# rfboard.net
KiCad netlist of a schematic drawn in EAGLE
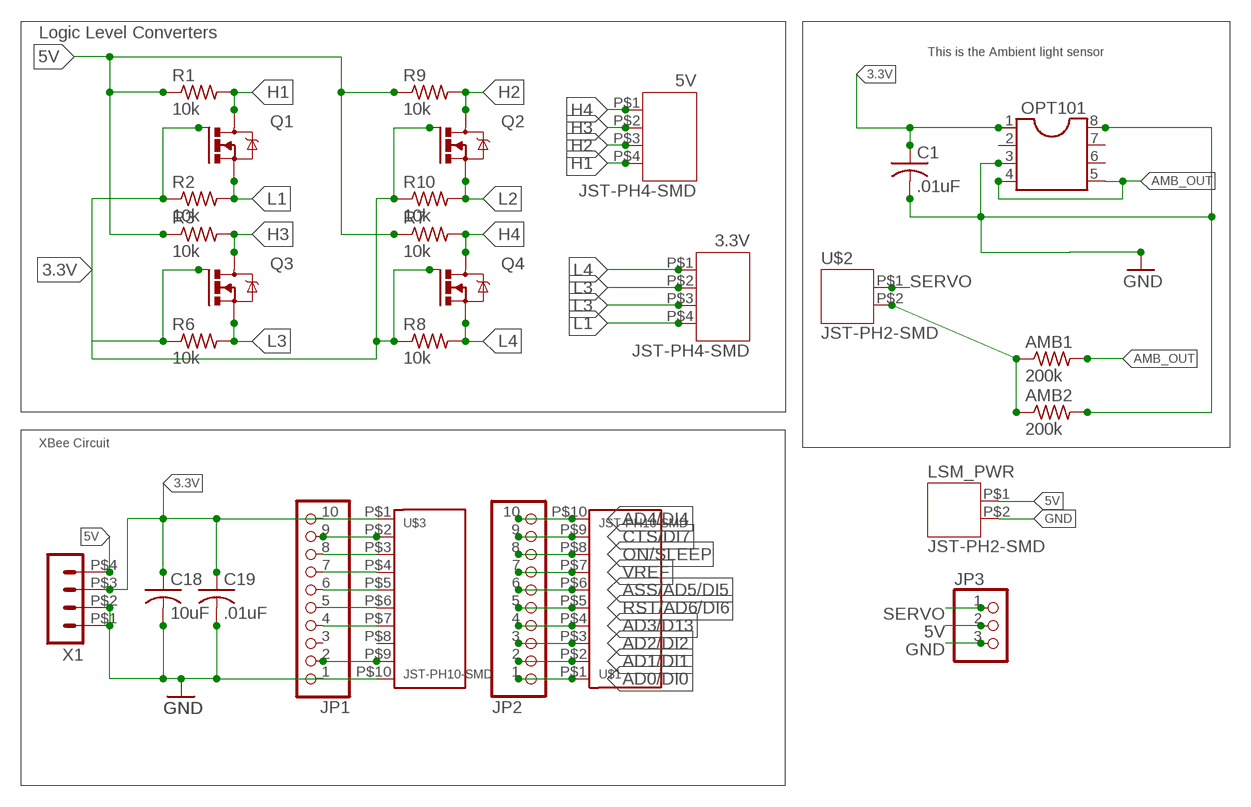
[diagram p0: schematic, sheet 1]

(export (version "E")
  (design (tool "Eeschema 10.0.6"))
  (components
    (comp (ref "3.3V")
      (value "JST-PH4-SMD")
      (footprint "eagle-import:JST-PH4-SMD")
      (libsource (lib "eagle-import") (part "JST-PH4-SMD"))
    )
    (comp (ref "5V")
      (value "JST-PH4-SMD")
      (footprint "eagle-import:JST-PH4-SMD")
      (libsource (lib "eagle-import") (part "JST-PH4-SMD"))
    )
    (comp (ref "AMB1")
      (value "200k")
      (footprint "eagle-import:R0805")
      (libsource (lib "eagle-import") (part "R-US_R0805"))
    )
    (comp (ref "AMB2")
      (value "200k")
      (footprint "eagle-import:R0805")
      (libsource (lib "eagle-import") (part "R-US_R0805"))
    )
    (comp (ref "C1")
      (value ".01uF")
      (footprint "eagle-import:C0805K")
      (libsource (lib "eagle-import") (part "C-USC0805K"))
    )
    (comp (ref "C18")
      (value "10uF")
      (footprint "eagle-import:C1206K")
      (libsource (lib "eagle-import") (part "C-USC1206K"))
    )
    (comp (ref "C19")
      (value ".01uF")
      (footprint "eagle-import:C0805K")
      (libsource (lib "eagle-import") (part "C-USC0805K"))
    )
    (comp (ref "JP1")
      (value "PINHD-1X10_2.00")
      (footprint "eagle-import:1X10M")
      (libsource (lib "eagle-import") (part "PINHD-1X10_2.00"))
    )
    (comp (ref "JP2")
      (value "PINHD-1X10_2.00")
      (footprint "eagle-import:1X10M")
      (libsource (lib "eagle-import") (part "PINHD-1X10_2.00"))
    )
    (comp (ref "JP3")
      (value "PINHD-1X3")
      (footprint "eagle-import:1X03")
      (libsource (lib "eagle-import") (part "PINHD-1X3"))
    )
    (comp (ref "LSM_PWR")
      (value "JST-PH2-SMD")
      (footprint "eagle-import:JST-PH2-SMD")
      (libsource (lib "eagle-import") (part "JST-PH2-SMD"))
    )
    (comp (ref "OPT101")
      (value "DIL8")
      (footprint "eagle-import:DIL08")
      (libsource (lib "eagle-import") (part "DIL8"))
    )
    (comp (ref "Q1")
      (value "IRLML5203")
      (footprint "eagle-import:MICRO3")
      (libsource (lib "eagle-import") (part "IRLML5203"))
    )
    (comp (ref "Q2")
      (value "IRLML5203")
      (footprint "eagle-import:MICRO3")
      (libsource (lib "eagle-import") (part "IRLML5203"))
    )
    (comp (ref "Q3")
      (value "IRLML5203")
      (footprint "eagle-import:MICRO3")
      (libsource (lib "eagle-import") (part "IRLML5203"))
    )
    (comp (ref "Q4")
      (value "IRLML5203")
      (footprint "eagle-import:MICRO3")
      (libsource (lib "eagle-import") (part "IRLML5203"))
    )
    (comp (ref "R1")
      (value "10k")
      (footprint "eagle-import:R0805")
      (libsource (lib "eagle-import") (part "R-US_R0805"))
    )
    (comp (ref "R2")
      (value "10k")
      (footprint "eagle-import:R0805")
      (libsource (lib "eagle-import") (part "R-US_R0805"))
    )
    (comp (ref "R3")
      (value "10k")
      (footprint "eagle-import:R0805")
      (libsource (lib "eagle-import") (part "R-US_R0805"))
    )
    (comp (ref "R6")
      (value "10k")
      (footprint "eagle-import:R0805")
      (libsource (lib "eagle-import") (part "R-US_R0805"))
    )
    (comp (ref "R7")
      (value "10k")
      (footprint "eagle-import:R0805")
      (libsource (lib "eagle-import") (part "R-US_R0805"))
    )
    (comp (ref "R8")
      (value "10k")
      (footprint "eagle-import:R0805")
      (libsource (lib "eagle-import") (part "R-US_R0805"))
    )
    (comp (ref "R9")
      (value "10k")
      (footprint "eagle-import:R0805")
      (libsource (lib "eagle-import") (part "R-US_R0805"))
    )
    (comp (ref "R10")
      (value "10k")
      (footprint "eagle-import:R0805")
      (libsource (lib "eagle-import") (part "R-US_R0805"))
    )
    (comp (ref "U$1")
      (value "JST-PH10-SMD")
      (footprint "eagle-import:JST-PH10-SMD")
      (libsource (lib "eagle-import") (part "JST-PH10-SMD"))
    )
    (comp (ref "U$2")
      (value "JST-PH2-SMD")
      (footprint "eagle-import:JST-PH2-SMD")
      (libsource (lib "eagle-import") (part "JST-PH2-SMD"))
    )
    (comp (ref "U$3")
      (value "JST-PH10-SMD")
      (footprint "eagle-import:JST-PH10-SMD")
      (libsource (lib "eagle-import") (part "JST-PH10-SMD"))
    )
    (comp (ref "X1")
      (value "HEADER_POS4_43045-0406")
      (footprint "eagle-import:43045-0406")
      (libsource (lib "eagle-import") (part "HEADER_POS4_?43045-0406"))
    )
  )
  (nets
    (net (code "1") (name "/SERVO") (class "Default")
      (node (ref "JP3") (pin "1") (pinfunction "1_1") (pintype "passive"))
      (node (ref "U$2") (pin "P$1") (pinfunction "1_P$1") (pintype "passive"))
    )
    (net (code "2") (name "3.3V") (class "Default")
      (node (ref "C1") (pin "1") (pinfunction "1_1") (pintype "passive"))
      (node (ref "C18") (pin "1") (pinfunction "1_1") (pintype "passive"))
      (node (ref "C19") (pin "1") (pinfunction "1_1") (pintype "passive"))
      (node (ref "JP1") (pin "10") (pinfunction "10_10") (pintype "passive"))
      (node (ref "OPT101") (pin "1") (pinfunction "1_1") (pintype "passive"))
      (node (ref "Q1") (pin "1") (pinfunction "G_1") (pintype "passive"))
      (node (ref "Q2") (pin "1") (pinfunction "G_1") (pintype "passive"))
      (node (ref "Q3") (pin "1") (pinfunction "G_1") (pintype "passive"))
      (node (ref "Q4") (pin "1") (pinfunction "G_1") (pintype "passive"))
      (node (ref "R10") (pin "1") (pinfunction "1_1") (pintype "passive"))
      (node (ref "R2") (pin "1") (pinfunction "1_1") (pintype "passive"))
      (node (ref "R6") (pin "1") (pinfunction "1_1") (pintype "passive"))
      (node (ref "R8") (pin "1") (pinfunction "1_1") (pintype "passive"))
      (node (ref "U$3") (pin "P$1") (pinfunction "P$1_P$1") (pintype "bidirectional"))
      (node (ref "X1") (pin "P$3") (pinfunction "3_P$3") (pintype "passive"))
    )
    (net (code "3") (name "5V") (class "Default")
      (node (ref "JP3") (pin "2") (pinfunction "2_2") (pintype "passive"))
      (node (ref "LSM_PWR") (pin "P$1") (pinfunction "1_P$1") (pintype "passive"))
      (node (ref "R1") (pin "1") (pinfunction "1_1") (pintype "passive"))
      (node (ref "R3") (pin "1") (pinfunction "1_1") (pintype "passive"))
      (node (ref "R7") (pin "1") (pinfunction "1_1") (pintype "passive"))
      (node (ref "R9") (pin "1") (pinfunction "1_1") (pintype "passive"))
      (node (ref "X1") (pin "P$4") (pinfunction "4_P$4") (pintype "passive"))
    )
    (net (code "4") (name "AD0{slash}DI0") (class "Default")
      (node (ref "JP2") (pin "1") (pinfunction "1_1") (pintype "passive"))
      (node (ref "U$1") (pin "P$1") (pinfunction "P$1_P$1") (pintype "bidirectional"))
    )
    (net (code "5") (name "AD1{slash}DI1") (class "Default")
      (node (ref "JP2") (pin "2") (pinfunction "2_2") (pintype "passive"))
      (node (ref "U$1") (pin "P$2") (pinfunction "P$2_P$2") (pintype "bidirectional"))
    )
    (net (code "6") (name "AD2{slash}DI2") (class "Default")
      (node (ref "JP2") (pin "3") (pinfunction "3_3") (pintype "passive"))
      (node (ref "U$1") (pin "P$3") (pinfunction "P$3_P$3") (pintype "bidirectional"))
    )
    (net (code "7") (name "AD3{slash}D13") (class "Default")
      (node (ref "JP2") (pin "4") (pinfunction "4_4") (pintype "passive"))
      (node (ref "U$1") (pin "P$4") (pinfunction "P$4_P$4") (pintype "bidirectional"))
    )
    (net (code "8") (name "AD4{slash}DI4") (class "Default")
      (node (ref "JP2") (pin "10") (pinfunction "10_10") (pintype "passive"))
      (node (ref "U$1") (pin "P$10") (pinfunction "P$10_P$10") (pintype "bidirectional"))
    )
    (net (code "9") (name "AMB_OUT") (class "Default")
      (node (ref "AMB1") (pin "2") (pinfunction "2_2") (pintype "passive"))
      (node (ref "OPT101") (pin "4") (pinfunction "4_4") (pintype "passive"))
      (node (ref "OPT101") (pin "5") (pinfunction "5_5") (pintype "passive"))
    )
    (net (code "10") (name "ASS{slash}AD5{slash}DI5") (class "Default")
      (node (ref "JP2") (pin "6") (pinfunction "6_6") (pintype "passive"))
      (node (ref "U$1") (pin "P$6") (pinfunction "P$6_P$6") (pintype "bidirectional"))
    )
    (net (code "11") (name "CTS{slash}DI7") (class "Default")
      (node (ref "JP2") (pin "9") (pinfunction "9_9") (pintype "passive"))
      (node (ref "U$1") (pin "P$9") (pinfunction "P$9_P$9") (pintype "bidirectional"))
    )
    (net (code "12") (name "GND") (class "Default")
      (node (ref "AMB2") (pin "2") (pinfunction "2_2") (pintype "passive"))
      (node (ref "C1") (pin "2") (pinfunction "2_2") (pintype "passive"))
      (node (ref "C18") (pin "2") (pinfunction "2_2") (pintype "passive"))
      (node (ref "C19") (pin "2") (pinfunction "2_2") (pintype "passive"))
      (node (ref "JP1") (pin "1") (pinfunction "1_1") (pintype "passive"))
      (node (ref "JP3") (pin "3") (pinfunction "3_3") (pintype "passive"))
      (node (ref "LSM_PWR") (pin "P$2") (pinfunction "2_P$2") (pintype "passive"))
      (node (ref "OPT101") (pin "3") (pinfunction "3_3") (pintype "passive"))
      (node (ref "OPT101") (pin "8") (pinfunction "8_8") (pintype "passive"))
      (node (ref "U$3") (pin "P$10") (pinfunction "P$10_P$10") (pintype "bidirectional"))
      (node (ref "X1") (pin "P$1") (pinfunction "1_P$1") (pintype "passive"))
      (node (ref "X1") (pin "P$2") (pinfunction "2_P$2") (pintype "passive"))
    )
    (net (code "13") (name "H1") (class "Default")
      (node (ref "5V") (pin "P$4") (pinfunction "4_P$4") (pintype "passive"))
      (node (ref "Q1") (pin "3") (pinfunction "D_3") (pintype "passive"))
      (node (ref "R1") (pin "2") (pinfunction "2_2") (pintype "passive"))
    )
    (net (code "14") (name "H2") (class "Default")
      (node (ref "5V") (pin "P$3") (pinfunction "3_P$3") (pintype "passive"))
      (node (ref "Q2") (pin "3") (pinfunction "D_3") (pintype "passive"))
      (node (ref "R9") (pin "2") (pinfunction "2_2") (pintype "passive"))
    )
    (net (code "15") (name "H3") (class "Default")
      (node (ref "5V") (pin "P$2") (pinfunction "2_P$2") (pintype "passive"))
      (node (ref "Q3") (pin "3") (pinfunction "D_3") (pintype "passive"))
      (node (ref "R3") (pin "2") (pinfunction "2_2") (pintype "passive"))
    )
    (net (code "16") (name "H4") (class "Default")
      (node (ref "5V") (pin "P$1") (pinfunction "1_P$1") (pintype "passive"))
      (node (ref "Q4") (pin "3") (pinfunction "D_3") (pintype "passive"))
      (node (ref "R7") (pin "2") (pinfunction "2_2") (pintype "passive"))
    )
    (net (code "17") (name "L1") (class "Default")
      (node (ref "3.3V") (pin "P$4") (pinfunction "4_P$4") (pintype "passive"))
      (node (ref "Q1") (pin "2") (pinfunction "S_2") (pintype "passive"))
      (node (ref "R2") (pin "2") (pinfunction "2_2") (pintype "passive"))
    )
    (net (code "18") (name "L2") (class "Default")
      (node (ref "3.3V") (pin "P$3") (pinfunction "3_P$3") (pintype "passive"))
      (node (ref "Q2") (pin "2") (pinfunction "S_2") (pintype "passive"))
      (node (ref "R10") (pin "2") (pinfunction "2_2") (pintype "passive"))
    )
    (net (code "19") (name "L3") (class "Default")
      (node (ref "3.3V") (pin "P$2") (pinfunction "2_P$2") (pintype "passive"))
      (node (ref "Q3") (pin "2") (pinfunction "S_2") (pintype "passive"))
      (node (ref "R6") (pin "2") (pinfunction "2_2") (pintype "passive"))
    )
    (net (code "20") (name "L4") (class "Default")
      (node (ref "3.3V") (pin "P$1") (pinfunction "1_P$1") (pintype "passive"))
      (node (ref "Q4") (pin "2") (pinfunction "S_2") (pintype "passive"))
      (node (ref "R8") (pin "2") (pinfunction "2_2") (pintype "passive"))
    )
    (net (code "21") (name "Net-(JP1-Pad2)") (class "Default")
      (node (ref "JP1") (pin "2") (pinfunction "2_2") (pintype "passive"))
      (node (ref "U$3") (pin "P$9") (pinfunction "P$9_P$9") (pintype "bidirectional"))
    )
    (net (code "22") (name "Net-(JP1-Pad4)") (class "Default")
      (node (ref "JP1") (pin "4") (pinfunction "4_4") (pintype "passive"))
      (node (ref "U$3") (pin "P$7") (pinfunction "P$7_P$7") (pintype "bidirectional"))
    )
    (net (code "23") (name "Net-(JP1-Pad5)") (class "Default")
      (node (ref "JP1") (pin "5") (pinfunction "5_5") (pintype "passive"))
      (node (ref "U$3") (pin "P$6") (pinfunction "P$6_P$6") (pintype "bidirectional"))
    )
    (net (code "24") (name "Net-(JP1-Pad6)") (class "Default")
      (node (ref "JP1") (pin "6") (pinfunction "6_6") (pintype "passive"))
      (node (ref "U$3") (pin "P$5") (pinfunction "P$5_P$5") (pintype "bidirectional"))
    )
    (net (code "25") (name "Net-(JP1-Pad7)") (class "Default")
      (node (ref "JP1") (pin "7") (pinfunction "7_7") (pintype "passive"))
      (node (ref "U$3") (pin "P$4") (pinfunction "P$4_P$4") (pintype "bidirectional"))
    )
    (net (code "26") (name "Net-(JP1-Pad8)") (class "Default")
      (node (ref "JP1") (pin "8") (pinfunction "8_8") (pintype "passive"))
      (node (ref "U$3") (pin "P$3") (pinfunction "P$3_P$3") (pintype "bidirectional"))
    )
    (net (code "27") (name "Net-(JP1-Pad9)") (class "Default")
      (node (ref "JP1") (pin "9") (pinfunction "9_9") (pintype "passive"))
      (node (ref "U$3") (pin "P$2") (pinfunction "P$2_P$2") (pintype "bidirectional"))
    )
    (net (code "28") (name "Net-(U$2-2)") (class "Default")
      (node (ref "AMB1") (pin "1") (pinfunction "1_1") (pintype "passive"))
      (node (ref "AMB2") (pin "1") (pinfunction "1_1") (pintype "passive"))
      (node (ref "U$2") (pin "P$2") (pinfunction "2_P$2") (pintype "passive"))
    )
    (net (code "29") (name "ON{slash}SLEEP") (class "Default")
      (node (ref "JP2") (pin "8") (pinfunction "8_8") (pintype "passive"))
      (node (ref "U$1") (pin "P$8") (pinfunction "P$8_P$8") (pintype "bidirectional"))
    )
    (net (code "30") (name "RST{slash}AD6{slash}DI6") (class "Default")
      (node (ref "JP2") (pin "5") (pinfunction "5_5") (pintype "passive"))
      (node (ref "U$1") (pin "P$5") (pinfunction "P$5_P$5") (pintype "bidirectional"))
    )
    (net (code "31") (name "VREF") (class "Default")
      (node (ref "JP2") (pin "7") (pinfunction "7_7") (pintype "passive"))
      (node (ref "U$1") (pin "P$7") (pinfunction "P$7_P$7") (pintype "bidirectional"))
    )
    (net (code "32") (name "unconnected-(JP1-Pad3)") (class "Default")
      (node (ref "JP1") (pin "3") (pinfunction "3_3") (pintype "passive"))
    )
    (net (code "33") (name "unconnected-(OPT101-Pad2)") (class "Default")
      (node (ref "OPT101") (pin "2") (pinfunction "2_2") (pintype "passive"))
    )
    (net (code "34") (name "unconnected-(OPT101-Pad6)") (class "Default")
      (node (ref "OPT101") (pin "6") (pinfunction "6_6") (pintype "passive"))
    )
    (net (code "35") (name "unconnected-(OPT101-Pad7)") (class "Default")
      (node (ref "OPT101") (pin "7") (pinfunction "7_7") (pintype "passive"))
    )
    (net (code "36") (name "unconnected-(U$3-PadP$8)") (class "Default")
      (node (ref "U$3") (pin "P$8") (pinfunction "P$8_P$8") (pintype "bidirectional"))
    )
  )
)
